# 10-SoC_CLOCK_AND_RESET.net
KiCad netlist of a schematic drawn in Altium Designer
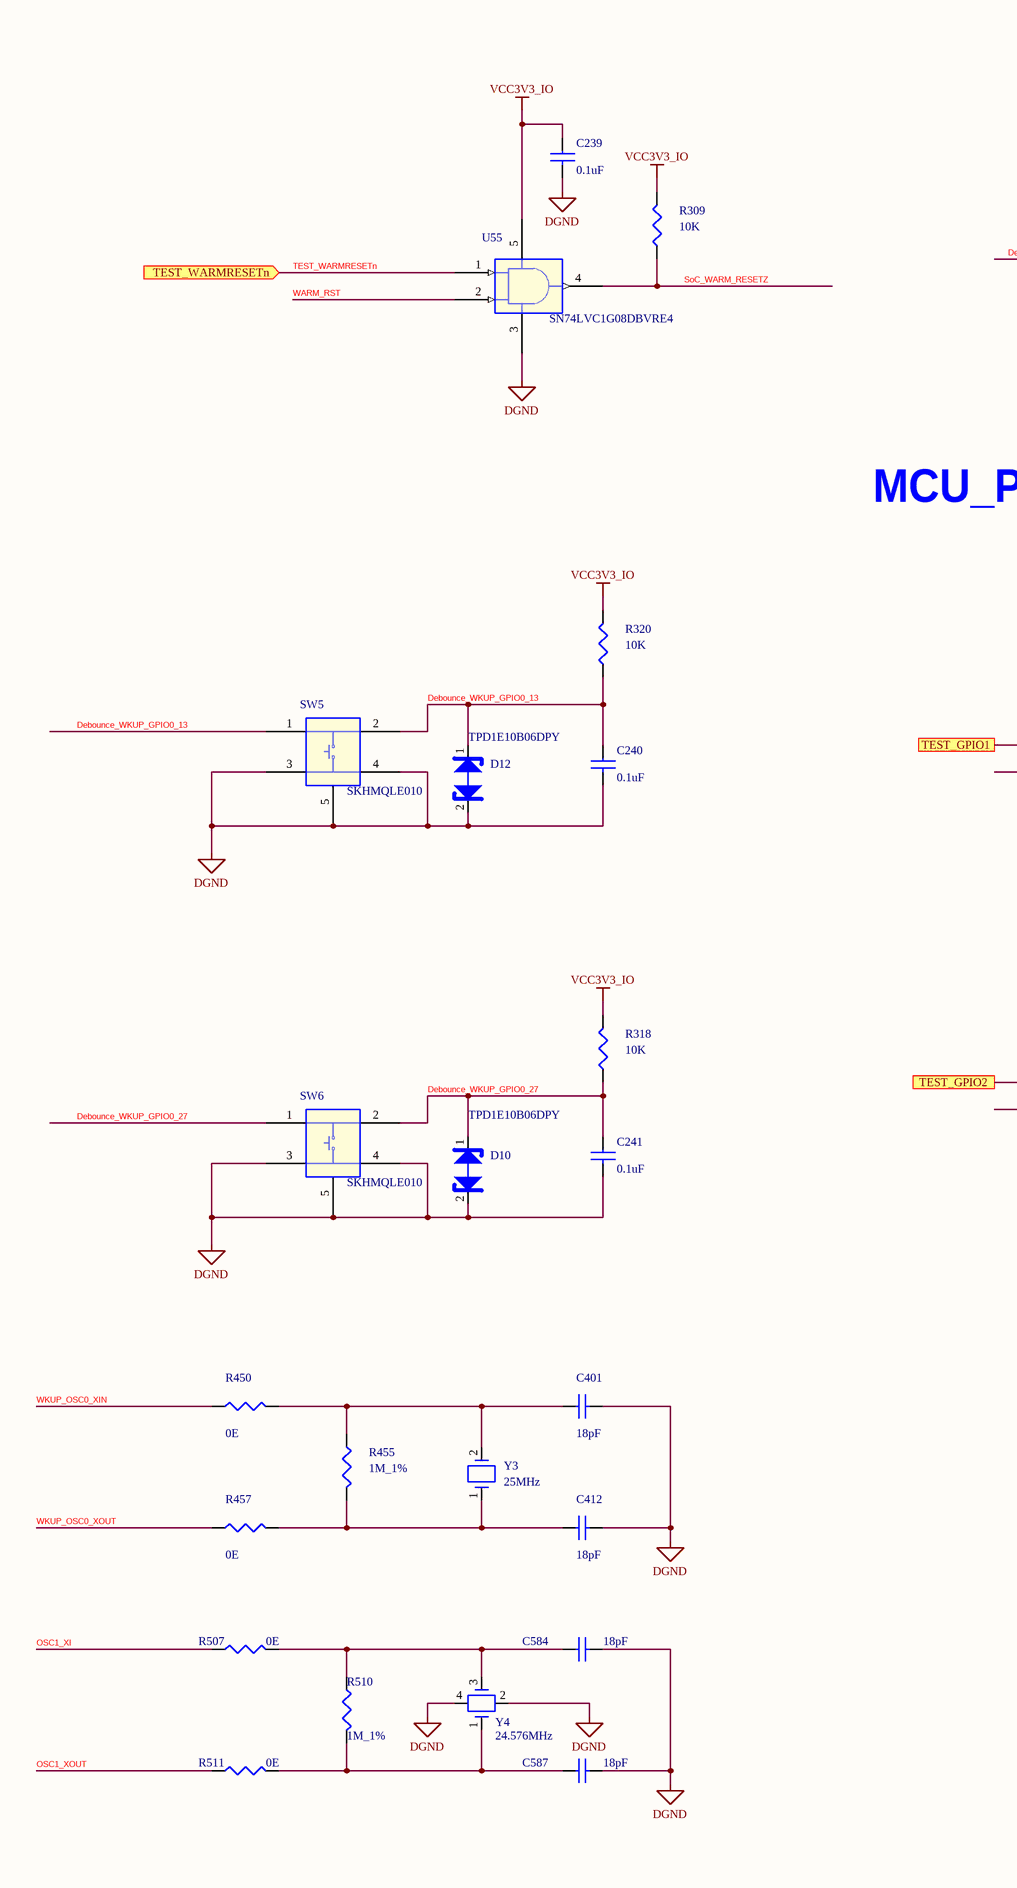
[diagram p0: 10-SoC CLOCK AND RESET.SchDoc, left]
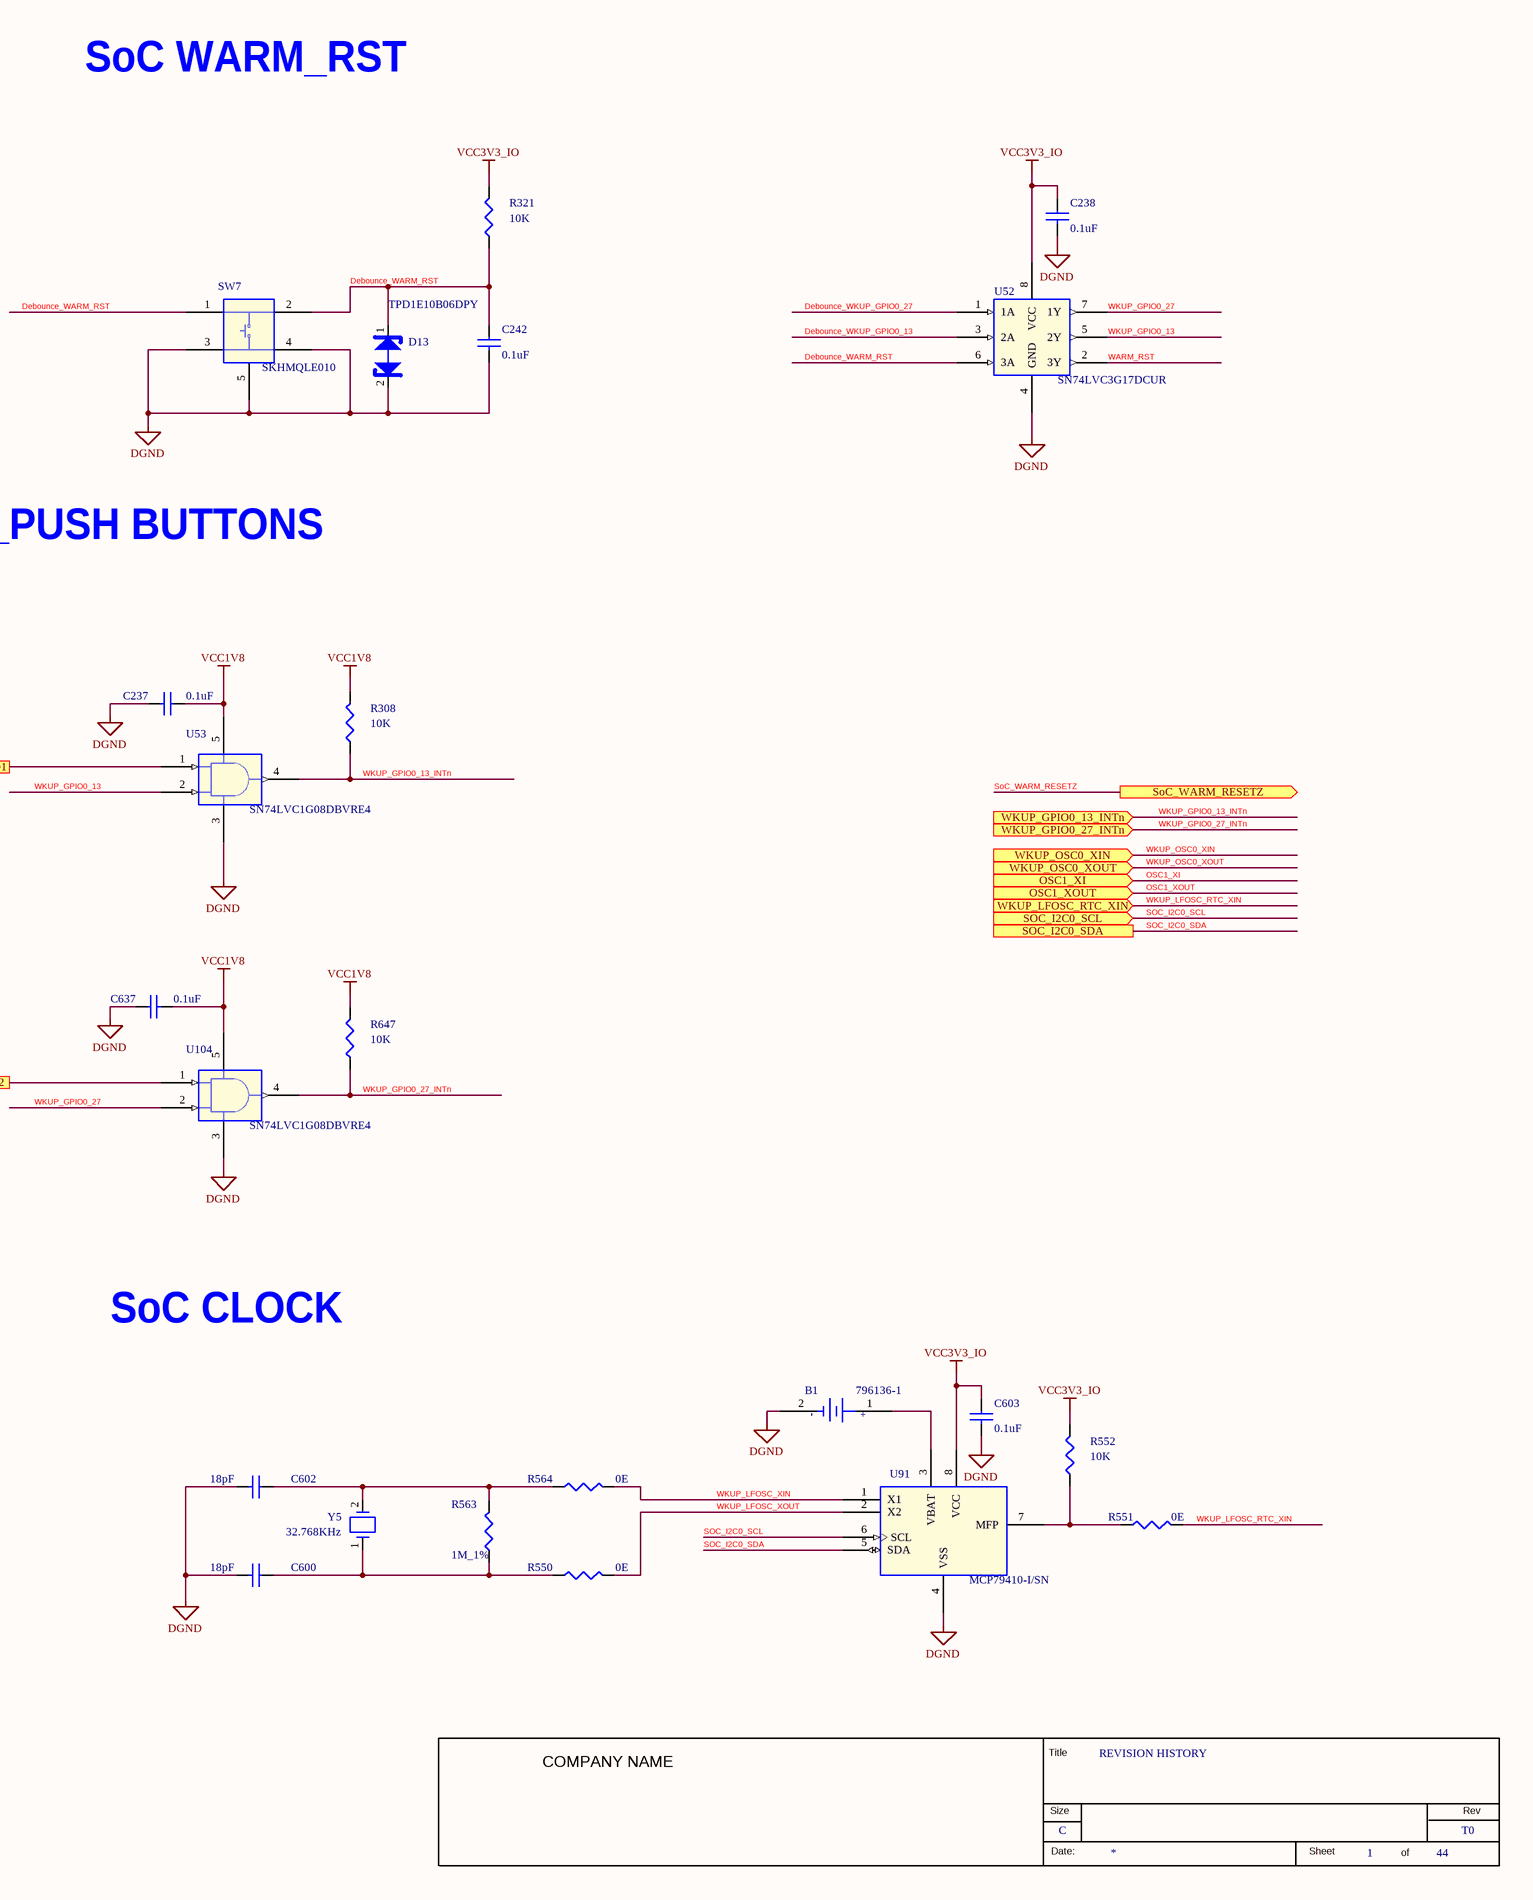
[diagram p1: 10-SoC CLOCK AND RESET.SchDoc, right]

(export (version "E")
  (design (tool "Eeschema 10.0.6"))
  (components
    (comp (ref "B1")
      (value "796136-1")
      (footprint "BATTH2_796136_1080X750_SMD_6-9")
      (description "BATTERY HOLDER COIN CELL TOP LOAD SMD")
      (fields (field (name "DISTRIBUTOR_PART_NUMBER") "A99327CT-ND") (field (name "VOLTAGE") "NA"))
      (libsource (lib "*") (part "BATTERY"))
    )
    (comp (ref "C237")
      (value "0.1uF")
      (footprint "CAP0201_0-5")
      (description "CAP CERAMIC 0.1uF 16V 10% X5R 0201")
      (fields (field (name "DISTRIBUTOR_PART_NUMBER") "490-16742-1-ND") (field (name "VOLTAGE") "16V"))
      (libsource (lib "*") (part "CAP_Dup5"))
    )
    (comp (ref "C238")
      (value "0.1uF")
      (footprint "CAP0201_0-5")
      (description "CAP CERAMIC 0.1uF 16V 10% X5R 0201")
      (fields (field (name "DISTRIBUTOR_PART_NUMBER") "490-16742-1-ND") (field (name "VOLTAGE") "16V"))
      (libsource (lib "*") (part "CAP_Dup5"))
    )
    (comp (ref "C239")
      (value "0.1uF")
      (footprint "CAP0201_0-5")
      (description "CAP CERAMIC 0.1uF 16V 10% X5R 0201")
      (fields (field (name "DISTRIBUTOR_PART_NUMBER") "490-16742-1-ND") (field (name "VOLTAGE") "16V"))
      (libsource (lib "*") (part "CAP_Dup5"))
    )
    (comp (ref "C240")
      (value "0.1uF")
      (footprint "CAP0201_0-5")
      (description "CAP CERAMIC 0.1uF 16V 10% X5R 0201")
      (fields
        (field (name "MISTRAL PART NO") "120009030072-R")
        (field (name "MFR_PART_NUMBER") "GRM033R61C104KE84J")
      )
      (libsource (lib "*") (part "CAP_Dup5"))
    )
    (comp (ref "C241")
      (value "0.1uF")
      (footprint "CAP0201_0-5")
      (description "CAP CERAMIC 0.1uF 16V 10% X5R 0201")
      (fields
        (field (name "MISTRAL PART NO") "120009030072-R")
        (field (name "MFR_PART_NUMBER") "GRM033R61C104KE84J")
      )
      (libsource (lib "*") (part "CAP_Dup5"))
    )
    (comp (ref "C242")
      (value "0.1uF")
      (footprint "CAP0201_0-5")
      (description "CAP CERAMIC 0.1uF 16V 10% X5R 0201")
      (fields (field (name "DISTRIBUTOR_PART_NUMBER") "490-16742-1-ND") (field (name "VOLTAGE") "16V"))
      (libsource (lib "*") (part "CAP_Dup5"))
    )
    (comp (ref "C401")
      (value "18pF")
      (footprint "CAP0402_0-75")
      (description "CAP CERAMIC 18pF 50V 5% C0G(NP0) 0402")
      (fields (field (name "DISTRIBUTOR_PART_NUMBER") "490-5858-1-ND") (field (name "VOLTAGE") "50V"))
      (libsource (lib "*") (part "CAP_Dup5"))
    )
    (comp (ref "C412")
      (value "18pF")
      (footprint "CAP0402_0-75")
      (description "CAP CERAMIC 18pF 50V 5% C0G(NP0) 0402")
      (fields (field (name "DISTRIBUTOR_PART_NUMBER") "490-5858-1-ND") (field (name "VOLTAGE") "50V"))
      (libsource (lib "*") (part "CAP_Dup5"))
    )
    (comp (ref "C584")
      (value "18pF")
      (footprint "CAP0402_0-75")
      (description "CAP CERAMIC 18pF 50V 5% C0G(NP0) 0402")
      (fields (field (name "DISTRIBUTOR_PART_NUMBER") "490-5858-1-ND") (field (name "VOLTAGE") "50V"))
      (libsource (lib "*") (part "CAP_Dup5"))
    )
    (comp (ref "C587")
      (value "18pF")
      (footprint "CAP0402_0-75")
      (description "CAP CERAMIC 18pF 50V 5% C0G(NP0) 0402")
      (fields (field (name "DISTRIBUTOR_PART_NUMBER") "490-5858-1-ND") (field (name "VOLTAGE") "50V"))
      (libsource (lib "*") (part "CAP_Dup5"))
    )
    (comp (ref "C600")
      (value "18pF")
      (footprint "CAP0402_0-75")
      (description "CAP CERAMIC 18pF 50V 5% C0G(NP0) 0402")
      (fields
        (field (name "MISTRAL PART NO") "120014050002-R")
        (field (name "MFR_PART_NUMBER") "GRM1555C1H180JA01D")
      )
      (libsource (lib "*") (part "CAP_Dup5"))
    )
    (comp (ref "C602")
      (value "18pF")
      (footprint "CAP0402_0-75")
      (description "CAP CERAMIC 18pF 50V 5% C0G(NP0) 0402")
      (fields (field (name "DISTRIBUTOR_PART_NUMBER") "490-5858-1-ND") (field (name "VOLTAGE") "50V"))
      (libsource (lib "*") (part "CAP_Dup5"))
    )
    (comp (ref "C603")
      (value "0.1uF")
      (footprint "CAP0201_0-5")
      (description "CAP CERAMIC 0.1uF 16V 10% X5R 0201")
      (fields
        (field (name "MISTRAL PART NO") "120009030072-R")
        (field (name "MFR_PART_NUMBER") "GRM033R61C104KE84J")
      )
      (libsource (lib "*") (part "CAP_Dup5"))
    )
    (comp (ref "C637")
      (value "0.1uF")
      (footprint "CAP0201_0-5")
      (description "CAP CERAMIC 0.1uF 16V 10% X5R 0201")
      (fields
        (field (name "MISTRAL PART NO") "120009030072-R")
        (field (name "MFR_PART_NUMBER") "GRM033R61C104KE84J")
      )
      (libsource (lib "*") (part "CAP_Dup5"))
    )
    (comp (ref "D10")
      (value "TPD1E10B06DPY")
      (footprint "DIO_DFN0402")
      (description "DIODE 1CH ESD PROTECTION SMD(0402)")
      (fields (field (name "MISTRAL PART NO") "130014110022-R") (field (name "TOLERANCE") "NA"))
      (libsource (lib "*") (part "DIODE_PESD"))
    )
    (comp (ref "D12")
      (value "TPD1E10B06DPY")
      (footprint "DIO_DFN0402")
      (description "DIODE 1CH ESD PROTECTION SMD(0402)")
      (fields (field (name "MISTRAL PART NO") "130014110022-R") (field (name "TOLERANCE") "NA"))
      (libsource (lib "*") (part "DIODE_PESD"))
    )
    (comp (ref "D13")
      (value "TPD1E10B06DPY")
      (footprint "DIO_DFN0402")
      (description "DIODE 1CH ESD PROTECTION SMD(0402)")
      (fields (field (name "DISTRIBUTOR_PART_NUMBER") "296-30406-1-ND") (field (name "VOLTAGE") "NA"))
      (libsource (lib "*") (part "DIODE_PESD"))
    )
    (comp (ref "R308")
      (value "10K")
      (footprint "RES0402_0-5")
      (description "RES 10K 1/16W 5% 0402")
      (fields
        (field (name "MISTRAL PART NO") "110009030208-R")
        (field (name "MFR_PART_NUMBER") "RC0402JR-0710KL")
      )
      (libsource (lib "*") (part "RESISTOR_Dup5"))
    )
    (comp (ref "R309")
      (value "10K")
      (footprint "RES0402_0-5")
      (description "RES 10K 1/16W 5% 0402")
      (fields (field (name "DISTRIBUTOR_PART_NUMBER") "311-10KJRCT-ND") (field (name "VOLTAGE") "NA"))
      (libsource (lib "*") (part "RESISTOR_Dup5"))
    )
    (comp (ref "R318")
      (value "10K")
      (footprint "RES0402_0-5")
      (description "RES 10K 1/16W 5% 0402")
      (fields (field (name "DISTRIBUTOR_PART_NUMBER") "311-10KJRCT-ND") (field (name "VOLTAGE") "NA"))
      (libsource (lib "*") (part "RESISTOR_Dup5"))
    )
    (comp (ref "R320")
      (value "10K")
      (footprint "RES0402_0-5")
      (description "RES 10K 1/16W 5% 0402")
      (fields (field (name "DISTRIBUTOR_PART_NUMBER") "311-10KJRCT-ND") (field (name "VOLTAGE") "NA"))
      (libsource (lib "*") (part "RESISTOR_Dup5"))
    )
    (comp (ref "R321")
      (value "10K")
      (footprint "RES0402_0-5")
      (description "RES 10K 1/16W 5% 0402")
      (fields (field (name "DISTRIBUTOR_PART_NUMBER") "311-10KJRCT-ND") (field (name "VOLTAGE") "NA"))
      (libsource (lib "*") (part "RESISTOR_Dup5"))
    )
    (comp (ref "R450")
      (value "0E")
      (footprint "RES0402_0-5")
      (description "RES 0E 1/16W 0402")
      (fields (field (name "DISTRIBUTOR_PART_NUMBER") "541-0.0JCT-ND") (field (name "VOLTAGE") "NA"))
      (libsource (lib "*") (part "RESISTOR_Dup4"))
    )
    (comp (ref "R455")
      (value "1M_1%")
      (footprint "RES0402")
      (description "RES 1M 1/16W 1% 0402")
      (fields (field (name "DISTRIBUTOR_PART_NUMBER") "RMCF0402FT1M00CT-ND") (field (name "VOLTAGE") "NA"))
      (libsource (lib "*") (part "RESISTOR_Dup5"))
    )
    (comp (ref "R457")
      (value "0E")
      (footprint "RES0402_0-5")
      (description "RES 0E 1/16W 0402")
      (fields (field (name "DISTRIBUTOR_PART_NUMBER") "541-0.0JCT-ND") (field (name "VOLTAGE") "NA"))
      (libsource (lib "*") (part "RESISTOR_Dup4"))
    )
    (comp (ref "R507")
      (value "0E")
      (footprint "RES0402_0-5")
      (description "RES 0E 1/16W 0402")
      (fields (field (name "DISTRIBUTOR_PART_NUMBER") "541-0.0JCT-ND") (field (name "VOLTAGE") "NA"))
      (libsource (lib "*") (part "RESISTOR_Dup4"))
    )
    (comp (ref "R510")
      (value "1M_1%")
      (footprint "RES0402")
      (description "RES 1M 1/16W 1% 0402")
      (fields
        (field (name "MISTRAL PART NO") "110014060045-R")
        (field (name "MFR_PART_NUMBER") "RMCF0402FT1M00")
      )
      (libsource (lib "*") (part "RESISTOR_Dup5"))
    )
    (comp (ref "R511")
      (value "0E")
      (footprint "RES0402_0-5")
      (description "RES 0E 1/16W 0402")
      (fields (field (name "DISTRIBUTOR_PART_NUMBER") "541-0.0JCT-ND") (field (name "VOLTAGE") "NA"))
      (libsource (lib "*") (part "RESISTOR_Dup4"))
    )
    (comp (ref "R550")
      (value "0E")
      (footprint "RES0402_0-5")
      (description "RES 0E 1/16W 0402")
      (fields
        (field (name "MISTRAL PART NO") "110010080019-P")
        (field (name "MFR_PART_NUMBER") "CRCW04020000Z0ED")
      )
      (libsource (lib "*") (part "RESISTOR_Dup4"))
    )
    (comp (ref "R551")
      (value "0E")
      (footprint "RES0402_0-5")
      (description "RES 0E 1/16W 0402")
      (fields
        (field (name "MISTRAL PART NO") "110010080019-P")
        (field (name "MFR_PART_NUMBER") "CRCW04020000Z0ED")
      )
      (libsource (lib "*") (part "RESISTOR_Dup4"))
    )
    (comp (ref "R552")
      (value "10K")
      (footprint "RES0402_0-5")
      (description "RES 10K 1/16W 5% 0402")
      (fields (field (name "DISTRIBUTOR_PART_NUMBER") "311-10KJRCT-ND") (field (name "VOLTAGE") "NA"))
      (libsource (lib "*") (part "RESISTOR_Dup5"))
    )
    (comp (ref "R563")
      (value "1M_1%")
      (footprint "RES0402")
      (description "RES 1M 1/16W 1% 0402")
      (fields
        (field (name "MISTRAL PART NO") "110014060045-R")
        (field (name "MFR_PART_NUMBER") "RMCF0402FT1M00")
      )
      (libsource (lib "*") (part "RESISTOR_Dup5"))
    )
    (comp (ref "R564")
      (value "0E")
      (footprint "RES0402_0-5")
      (description "RES 0E 1/16W 0402")
      (fields (field (name "DISTRIBUTOR_PART_NUMBER") "541-0.0JCT-ND") (field (name "VOLTAGE") "NA"))
      (libsource (lib "*") (part "RESISTOR_Dup4"))
    )
    (comp (ref "R647")
      (value "10K")
      (footprint "RES0402_0-5")
      (description "RES 10K 1/16W 5% 0402")
      (fields
        (field (name "MISTRAL PART NO") "110009030208-R")
        (field (name "MFR_PART_NUMBER") "RC0402JR-0710KL")
      )
      (libsource (lib "*") (part "RESISTOR_Dup5"))
    )
    (comp (ref "SW5")
      (value "SKHMQLE010")
      (footprint "SW4_SKHMQLE010_240X260_SMD_3-1")
      (description "SWITCH TACTILE SPST ST SMD")
      (fields (field (name "DISTRIBUTOR_PART_NUMBER") "688-SKHMQLE010") (field (name "VOLTAGE") "NA"))
      (libsource (lib "*") (part "SW4_SKHUPLE010"))
    )
    (comp (ref "SW6")
      (value "SKHMQLE010")
      (footprint "SW4_SKHMQLE010_240X260_SMD_3-1")
      (description "SWITCH TACTILE SPST ST SMD")
      (fields (field (name "MISTRAL PART NO") "130017100007-R") (field (name "TOLERANCE") "NA"))
      (libsource (lib "*") (part "SW4_SKHUPLE010"))
    )
    (comp (ref "SW7")
      (value "SKHMQLE010")
      (footprint "SW4_SKHMQLE010_240X260_SMD_3-1")
      (description "SWITCH TACTILE SPST ST SMD")
      (fields (field (name "DISTRIBUTOR_PART_NUMBER") "688-SKHMQLE010") (field (name "VOLTAGE") "NA"))
      (libsource (lib "*") (part "SW4_SKHUPLE010"))
    )
    (comp (ref "U52")
      (value "SN74LVC3G17DCUR")
      (footprint "VSSOP8_19-68_85X95_0-9")
      (description "IC TRIPLE SCHMITT-TRIGGER BUFFER VSSOP8")
      (fields (field (name "MISTRAL PART NO") "141017090019-R") (field (name "TOLERANCE") "NA"))
      (libsource (lib "*") (part "SN74LVC3G17DCUR_VSSOP8"))
    )
    (comp (ref "U53")
      (value "SN74LVC1G08DBVRE4")
      (footprint "SOT23-5")
      (description "IC SINGLE 2-INPUT POSITIVE AND GATE SOT23-5")
      (fields
        (field (name "DISTRIBUTOR_PART_NUMBER") "SN74LVC1G08DBVRE4-ND")
        (field (name "MISTRAL PART NO") "141009060026-R")
      )
      (libsource (lib "*") (part "SN74LVC1G08DBVRE4_SOT23-5"))
    )
    (comp (ref "U55")
      (value "SN74LVC1G08DBVRE4")
      (footprint "SOT23-5")
      (description "IC SINGLE 2-INPUT POSITIVE AND GATE SOT23-5")
      (fields
        (field (name "DISTRIBUTOR_PART_NUMBER") "SN74LVC1G08DBVRE4-ND")
        (field (name "MISTRAL PART NO") "141009060026-R")
      )
      (libsource (lib "*") (part "SN74LVC1G08DBVRE4_SOT23-5"))
    )
    (comp (ref "U91")
      (value "MCP79410-I/SN")
      (footprint "SOIC8_1-8")
      (description "IC BATTERY-BACKED I2C RTCC WITH SRAM,EEPROM SOIC8")
      (fields (field (name "DISTRIBUTOR_PART_NUMBER") "MCP79410-I/SN-ND") (field (name "VOLTAGE") "NA"))
      (libsource (lib "*") (part "MCP79410_SOIC8"))
    )
    (comp (ref "U104")
      (value "SN74LVC1G08DBVRE4")
      (footprint "SOT23-5")
      (description "IC SINGLE 2-INPUT POSITIVE AND GATE SOT23-5")
      (fields
        (field (name "DISTRIBUTOR_PART_NUMBER") "SN74LVC1G08DBVRE4-ND")
        (field (name "MISTRAL PART NO") "141009060026-R")
      )
      (libsource (lib "*") (part "SN74LVC1G08DBVRE4_SOT23-5"))
    )
    (comp (ref "Y3")
      (value "25MHz")
      (footprint "XTAL_ABM3_210X130_SMD")
      (description "CRY 25MHz SMD")
      (fields
        (field (name "MISTRAL PART NO") "130011100003-R")
        (field (name "MFR_PART_NUMBER") "445I23D25M00000")
      )
      (libsource (lib "*") (part "CRY"))
    )
    (comp (ref "Y4")
      (value "24.576MHz")
      (footprint "XTAL4_TXC_130X100_SMD_0-8")
      (description "CRY 24.576MHz 18pF SMD")
      (fields
        (field (name "MISTRAL PART NO") "130018010021-R")
        (field (name "MFR_PART_NUMBER") "7M-24.576MAAJ-T")
      )
      (libsource (lib "*") (part "CRY4_13"))
    )
    (comp (ref "Y5")
      (value "32.768KHz")
      (footprint "XTAL_ABS07_130X60_SMD_0-9")
      (description "CRY 32.768KHz 12.5pF SMD")
      (fields
        (field (name "MISTRAL PART NO") "130009030082-R")
        (field (name "MFR_PART_NUMBER") "ABS07-32.768KHZ-T")
      )
      (libsource (lib "*") (part "CRY"))
    )
  )
  (nets
    (net (code "1") (name "/Debounce_WARM_RST") (class "Default")
      (node (ref "C242") (pin "1") (pinfunction "1_1") (pintype "passive"))
      (node (ref "D13") (pin "1") (pinfunction "K_1") (pintype "passive"))
      (node (ref "R321") (pin "1") (pinfunction "1_1") (pintype "passive"))
      (node (ref "SW7") (pin "1") (pinfunction "1_1") (pintype "passive"))
      (node (ref "SW7") (pin "2") (pinfunction "2_2") (pintype "passive"))
      (node (ref "U52") (pin "6") (pinfunction "3A_6") (pintype "input"))
    )
    (net (code "2") (name "/Debounce_WKUP_GPIO0_13") (class "Default")
      (node (ref "C240") (pin "1") (pinfunction "1_1") (pintype "passive"))
      (node (ref "D12") (pin "1") (pinfunction "K_1") (pintype "passive"))
      (node (ref "R320") (pin "1") (pinfunction "1_1") (pintype "passive"))
      (node (ref "SW5") (pin "1") (pinfunction "1_1") (pintype "passive"))
      (node (ref "SW5") (pin "2") (pinfunction "2_2") (pintype "passive"))
      (node (ref "U52") (pin "3") (pinfunction "2A_3") (pintype "input"))
    )
    (net (code "3") (name "/Debounce_WKUP_GPIO0_27") (class "Default")
      (node (ref "C241") (pin "1") (pinfunction "1_1") (pintype "passive"))
      (node (ref "D10") (pin "1") (pinfunction "K_1") (pintype "passive"))
      (node (ref "R318") (pin "1") (pinfunction "1_1") (pintype "passive"))
      (node (ref "SW6") (pin "1") (pinfunction "1_1") (pintype "passive"))
      (node (ref "SW6") (pin "2") (pinfunction "2_2") (pintype "passive"))
      (node (ref "U52") (pin "1") (pinfunction "1A_1") (pintype "input"))
    )
    (net (code "4") (name "/OSC1_XI") (class "Default")
      (node (ref "R507") (pin "1") (pinfunction "1_1") (pintype "passive"))
    )
    (net (code "5") (name "/OSC1_XOUT") (class "Default")
      (node (ref "R511") (pin "1") (pinfunction "1_1") (pintype "passive"))
    )
    (net (code "6") (name "/SOC_I2C0_SCL") (class "Default")
      (node (ref "U91") (pin "6") (pinfunction "SCL_6") (pintype "input"))
    )
    (net (code "7") (name "/SOC_I2C0_SDA") (class "Default")
      (node (ref "U91") (pin "5") (pinfunction "SDA_5") (pintype "bidirectional"))
    )
    (net (code "8") (name "/SoC_WARM_RESETZ") (class "Default")
      (node (ref "R309") (pin "1") (pinfunction "1_1") (pintype "passive"))
      (node (ref "U55") (pin "4") (pinfunction "Y_4") (pintype "output"))
    )
    (net (code "9") (name "/TEST_GPIO1") (class "Default")
      (node (ref "U53") (pin "1") (pinfunction "A_1") (pintype "input"))
    )
    (net (code "10") (name "/TEST_GPIO2") (class "Default")
      (node (ref "U104") (pin "1") (pinfunction "A_1") (pintype "input"))
    )
    (net (code "11") (name "/TEST_WARMRESETn") (class "Default")
      (node (ref "U55") (pin "1") (pinfunction "A_1") (pintype "input"))
    )
    (net (code "12") (name "/WARM_RST") (class "Default")
      (node (ref "U52") (pin "2") (pinfunction "3Y_2") (pintype "output"))
      (node (ref "U55") (pin "2") (pinfunction "B_2") (pintype "input"))
    )
    (net (code "13") (name "/WKUP_GPIO0_13") (class "Default")
      (node (ref "U52") (pin "5") (pinfunction "2Y_5") (pintype "output"))
      (node (ref "U53") (pin "2") (pinfunction "B_2") (pintype "input"))
    )
    (net (code "14") (name "/WKUP_GPIO0_13_INTn") (class "Default")
      (node (ref "R308") (pin "1") (pinfunction "1_1") (pintype "passive"))
      (node (ref "U53") (pin "4") (pinfunction "Y_4") (pintype "output"))
    )
    (net (code "15") (name "/WKUP_GPIO0_27") (class "Default")
      (node (ref "U104") (pin "2") (pinfunction "B_2") (pintype "input"))
      (node (ref "U52") (pin "7") (pinfunction "1Y_7") (pintype "output"))
    )
    (net (code "16") (name "/WKUP_GPIO0_27_INTn") (class "Default")
      (node (ref "R647") (pin "1") (pinfunction "1_1") (pintype "passive"))
      (node (ref "U104") (pin "4") (pinfunction "Y_4") (pintype "output"))
    )
    (net (code "17") (name "/WKUP_LFOSC_RTC_XIN") (class "Default")
      (node (ref "R551") (pin "2") (pinfunction "2_2") (pintype "passive"))
    )
    (net (code "18") (name "/WKUP_LFOSC_XIN") (class "Default")
      (node (ref "R564") (pin "1") (pinfunction "1_1") (pintype "passive"))
      (node (ref "U91") (pin "1") (pinfunction "X1_1") (pintype "passive"))
    )
    (net (code "19") (name "/WKUP_LFOSC_XOUT") (class "Default")
      (node (ref "R550") (pin "1") (pinfunction "1_1") (pintype "passive"))
      (node (ref "U91") (pin "2") (pinfunction "X2_2") (pintype "passive"))
    )
    (net (code "20") (name "/WKUP_OSC0_XIN") (class "Default")
      (node (ref "R450") (pin "1") (pinfunction "1_1") (pintype "passive"))
    )
    (net (code "21") (name "/WKUP_OSC0_XOUT") (class "Default")
      (node (ref "R457") (pin "1") (pinfunction "1_1") (pintype "passive"))
    )
    (net (code "22") (name "DGND") (class "Default")
      (node (ref "B1") (pin "2") (pinfunction "-_2") (pintype "passive"))
      (node (ref "C237") (pin "2") (pinfunction "2_2") (pintype "passive"))
      (node (ref "C238") (pin "2") (pinfunction "2_2") (pintype "passive"))
      (node (ref "C239") (pin "2") (pinfunction "2_2") (pintype "passive"))
      (node (ref "C240") (pin "2") (pinfunction "2_2") (pintype "passive"))
      (node (ref "C241") (pin "2") (pinfunction "2_2") (pintype "passive"))
      (node (ref "C242") (pin "2") (pinfunction "2_2") (pintype "passive"))
      (node (ref "C401") (pin "2") (pinfunction "2_2") (pintype "passive"))
      (node (ref "C412") (pin "2") (pinfunction "2_2") (pintype "passive"))
      (node (ref "C584") (pin "2") (pinfunction "2_2") (pintype "passive"))
      (node (ref "C587") (pin "2") (pinfunction "2_2") (pintype "passive"))
      (node (ref "C600") (pin "2") (pinfunction "2_2") (pintype "passive"))
      (node (ref "C602") (pin "2") (pinfunction "2_2") (pintype "passive"))
      (node (ref "C603") (pin "2") (pinfunction "2_2") (pintype "passive"))
      (node (ref "C637") (pin "1") (pinfunction "1_1") (pintype "passive"))
      (node (ref "D10") (pin "2") (pinfunction "A_2") (pintype "passive"))
      (node (ref "D12") (pin "2") (pinfunction "A_2") (pintype "passive"))
      (node (ref "D13") (pin "2") (pinfunction "A_2") (pintype "passive"))
      (node (ref "SW5") (pin "3") (pinfunction "3_3") (pintype "passive"))
      (node (ref "SW5") (pin "4") (pinfunction "4_4") (pintype "passive"))
      (node (ref "SW5") (pin "5") (pinfunction "GND_5") (pintype "power_in"))
      (node (ref "SW6") (pin "3") (pinfunction "3_3") (pintype "passive"))
      (node (ref "SW6") (pin "4") (pinfunction "4_4") (pintype "passive"))
      (node (ref "SW6") (pin "5") (pinfunction "GND_5") (pintype "power_in"))
      (node (ref "SW7") (pin "3") (pinfunction "3_3") (pintype "passive"))
      (node (ref "SW7") (pin "4") (pinfunction "4_4") (pintype "passive"))
      (node (ref "SW7") (pin "5") (pinfunction "GND_5") (pintype "power_in"))
      (node (ref "U104") (pin "3") (pinfunction "GND_3") (pintype "power_in"))
      (node (ref "U52") (pin "4") (pinfunction "GND_4") (pintype "power_in"))
      (node (ref "U53") (pin "3") (pinfunction "GND_3") (pintype "power_in"))
      (node (ref "U55") (pin "3") (pinfunction "GND_3") (pintype "power_in"))
      (node (ref "U91") (pin "4") (pinfunction "VSS_4") (pintype "power_in"))
      (node (ref "Y4") (pin "2") (pinfunction "2_2") (pintype "passive"))
      (node (ref "Y4") (pin "4") (pinfunction "4_4") (pintype "passive"))
    )
    (net (code "23") (name "Net-(B1-+)") (class "Default")
      (node (ref "B1") (pin "1") (pinfunction "+_1") (pintype "passive"))
      (node (ref "U91") (pin "3") (pinfunction "VBAT_3") (pintype "power_in"))
    )
    (net (code "24") (name "Net-(C401-Pad1)") (class "Default")
      (node (ref "C401") (pin "1") (pinfunction "1_1") (pintype "passive"))
      (node (ref "R450") (pin "2") (pinfunction "2_2") (pintype "passive"))
      (node (ref "R455") (pin "1") (pinfunction "1_1") (pintype "passive"))
      (node (ref "Y3") (pin "2") (pinfunction "2_2") (pintype "passive"))
    )
    (net (code "25") (name "Net-(C412-Pad1)") (class "Default")
      (node (ref "C412") (pin "1") (pinfunction "1_1") (pintype "passive"))
      (node (ref "R455") (pin "2") (pinfunction "2_2") (pintype "passive"))
      (node (ref "R457") (pin "2") (pinfunction "2_2") (pintype "passive"))
      (node (ref "Y3") (pin "1") (pinfunction "1_1") (pintype "passive"))
    )
    (net (code "26") (name "Net-(C584-Pad1)") (class "Default")
      (node (ref "C584") (pin "1") (pinfunction "1_1") (pintype "passive"))
      (node (ref "R507") (pin "2") (pinfunction "2_2") (pintype "passive"))
      (node (ref "R510") (pin "1") (pinfunction "1_1") (pintype "passive"))
      (node (ref "Y4") (pin "3") (pinfunction "3_3") (pintype "passive"))
    )
    (net (code "27") (name "Net-(C587-Pad1)") (class "Default")
      (node (ref "C587") (pin "1") (pinfunction "1_1") (pintype "passive"))
      (node (ref "R510") (pin "2") (pinfunction "2_2") (pintype "passive"))
      (node (ref "R511") (pin "2") (pinfunction "2_2") (pintype "passive"))
      (node (ref "Y4") (pin "1") (pinfunction "1_1") (pintype "passive"))
    )
    (net (code "28") (name "Net-(C600-Pad1)") (class "Default")
      (node (ref "C600") (pin "1") (pinfunction "1_1") (pintype "passive"))
      (node (ref "R550") (pin "2") (pinfunction "2_2") (pintype "passive"))
      (node (ref "R563") (pin "2") (pinfunction "2_2") (pintype "passive"))
      (node (ref "Y5") (pin "1") (pinfunction "1_1") (pintype "passive"))
    )
    (net (code "29") (name "Net-(C602-Pad1)") (class "Default")
      (node (ref "C602") (pin "1") (pinfunction "1_1") (pintype "passive"))
      (node (ref "R563") (pin "1") (pinfunction "1_1") (pintype "passive"))
      (node (ref "R564") (pin "2") (pinfunction "2_2") (pintype "passive"))
      (node (ref "Y5") (pin "2") (pinfunction "2_2") (pintype "passive"))
    )
    (net (code "30") (name "Net-(U91-MFP)") (class "Default")
      (node (ref "R551") (pin "1") (pinfunction "1_1") (pintype "passive"))
      (node (ref "R552") (pin "1") (pinfunction "1_1") (pintype "passive"))
      (node (ref "U91") (pin "7") (pinfunction "MFP_7") (pintype "passive"))
    )
    (net (code "31") (name "VCC1V8") (class "Default")
      (node (ref "C237") (pin "1") (pinfunction "1_1") (pintype "passive"))
      (node (ref "C637") (pin "2") (pinfunction "2_2") (pintype "passive"))
      (node (ref "R308") (pin "2") (pinfunction "2_2") (pintype "passive"))
      (node (ref "R647") (pin "2") (pinfunction "2_2") (pintype "passive"))
      (node (ref "U104") (pin "5") (pinfunction "VCC_5") (pintype "power_in"))
      (node (ref "U53") (pin "5") (pinfunction "VCC_5") (pintype "power_in"))
    )
    (net (code "32") (name "VCC3V3_IO") (class "Default")
      (node (ref "C238") (pin "1") (pinfunction "1_1") (pintype "passive"))
      (node (ref "C239") (pin "1") (pinfunction "1_1") (pintype "passive"))
      (node (ref "C603") (pin "1") (pinfunction "1_1") (pintype "passive"))
      (node (ref "R309") (pin "2") (pinfunction "2_2") (pintype "passive"))
      (node (ref "R318") (pin "2") (pinfunction "2_2") (pintype "passive"))
      (node (ref "R320") (pin "2") (pinfunction "2_2") (pintype "passive"))
      (node (ref "R321") (pin "2") (pinfunction "2_2") (pintype "passive"))
      (node (ref "R552") (pin "2") (pinfunction "2_2") (pintype "passive"))
      (node (ref "U52") (pin "8") (pinfunction "VCC_8") (pintype "power_in"))
      (node (ref "U55") (pin "5") (pinfunction "VCC_5") (pintype "power_in"))
      (node (ref "U91") (pin "8") (pinfunction "VCC_8") (pintype "power_in"))
    )
  )
)
